# ATMEGA2560.net
KiCad netlist of a schematic drawn in Altium Designer
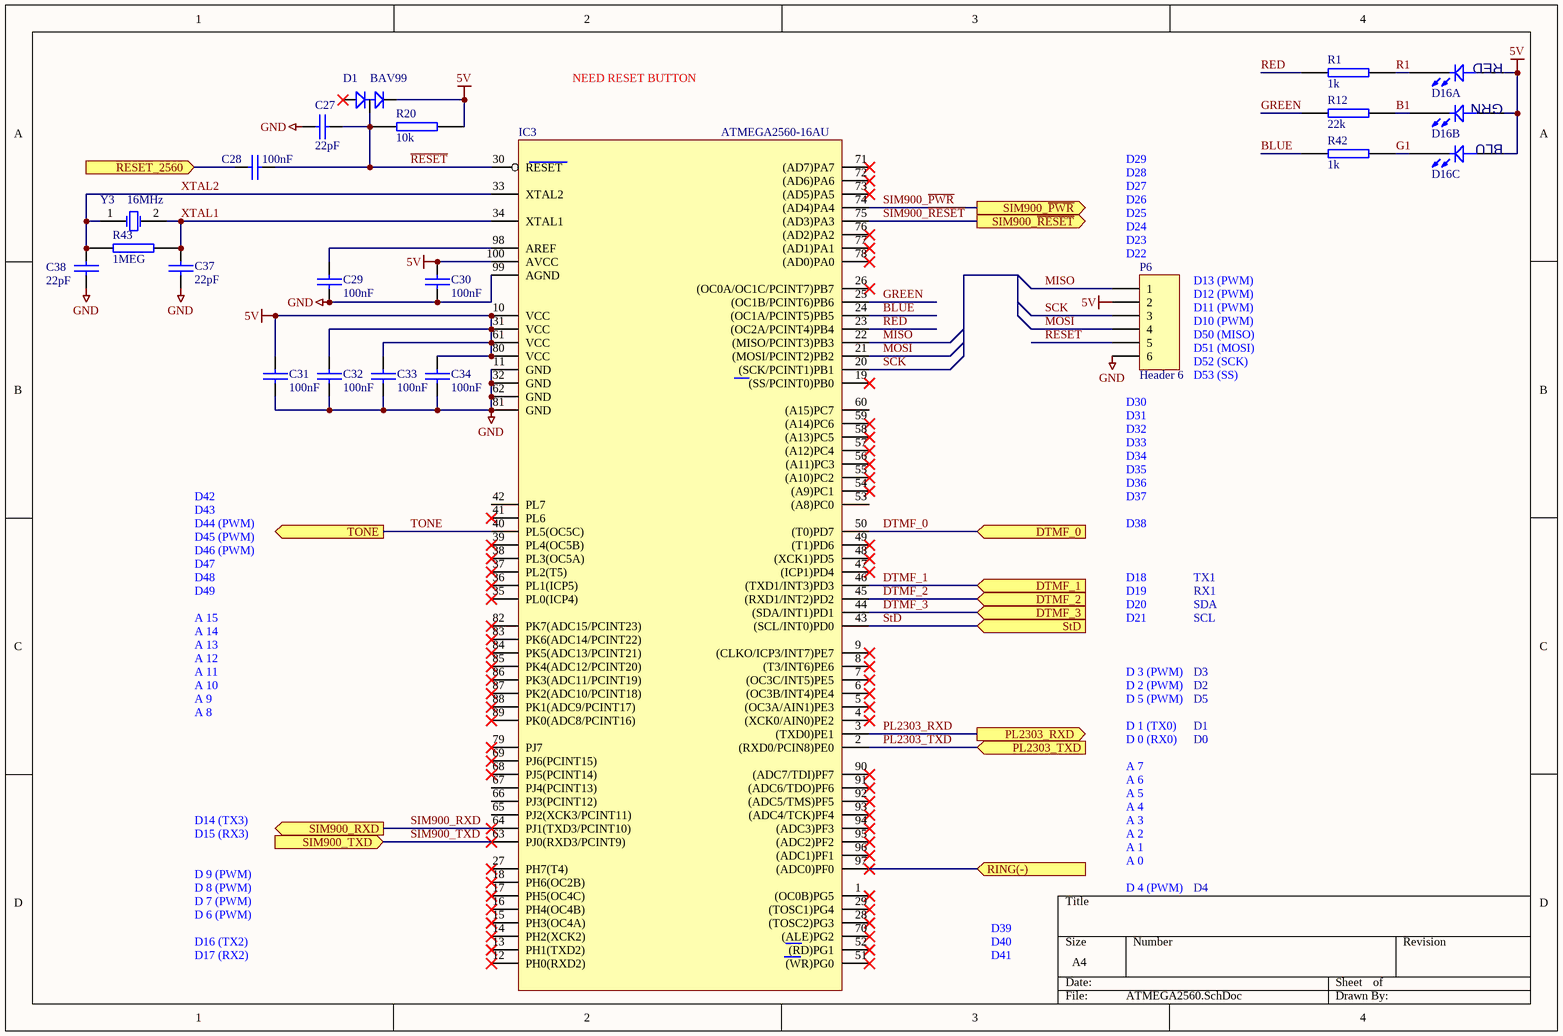
[diagram p0: ATMEGA2560.SchDoc]

(export (version "E")
  (design (tool "Eeschema 10.0.6"))
  (components
    (comp (ref "C27")
      (value "22pF")
      (footprint "CAP (3D) - 0603")
      (description "CAPACITOR SMD 0603")
      (fields (field (name "MOUSER PART NO.") "81-GCM188R71C104KA7D") (field (name "MANUFACTURER") "Murata"))
      (libsource (lib "NASCO Capacitors") (part "CAP SMD 0603 100nF"))
    )
    (comp (ref "C28")
      (value "100nF")
      (footprint "CAP (3D) - 0603")
      (description "CAPACITOR SMD 0603")
      (fields (field (name "MOUSER PART NO.") "81-GCM188R71C104KA7D") (field (name "MANUFACTURER") "Murata"))
      (libsource (lib "NASCO Capacitors") (part "CAP SMD 0603 100nF"))
    )
    (comp (ref "C29")
      (value "100nF")
      (footprint "CAP (3D) - 0603")
      (description "CAPACITOR SMD 0603")
      (fields (field (name "MOUSER PART NO.") "81-GCM188R71C104KA7D") (field (name "MANUFACTURER") "Murata"))
      (libsource (lib "NASCO Capacitors") (part "CAP SMD 0603 100nF"))
    )
    (comp (ref "C30")
      (value "100nF")
      (footprint "CAP (3D) - 0603")
      (description "CAPACITOR SMD 0603")
      (fields (field (name "MOUSER PART NO.") "81-GCM188R71C104KA7D") (field (name "MANUFACTURER") "Murata"))
      (libsource (lib "NASCO Capacitors") (part "CAP SMD 0603 100nF"))
    )
    (comp (ref "C31")
      (value "100nF")
      (footprint "CAP (3D) - 0603")
      (description "CAPACITOR SMD 0603")
      (fields (field (name "MOUSER PART NO.") "81-GCM188R71C104KA7D") (field (name "MANUFACTURER") "Murata"))
      (libsource (lib "NASCO Capacitors") (part "CAP SMD 0603 100nF"))
    )
    (comp (ref "C32")
      (value "100nF")
      (footprint "CAP (3D) - 0603")
      (description "CAPACITOR SMD 0603")
      (fields (field (name "MOUSER PART NO.") "81-GCM188R71C104KA7D") (field (name "MANUFACTURER") "Murata"))
      (libsource (lib "NASCO Capacitors") (part "CAP SMD 0603 100nF"))
    )
    (comp (ref "C33")
      (value "100nF")
      (footprint "CAP (3D) - 0603")
      (description "CAPACITOR SMD 0603")
      (fields (field (name "MOUSER PART NO.") "81-GCM188R71C104KA7D") (field (name "MANUFACTURER") "Murata"))
      (libsource (lib "NASCO Capacitors") (part "CAP SMD 0603 100nF"))
    )
    (comp (ref "C34")
      (value "100nF")
      (footprint "CAP (3D) - 0603")
      (description "CAPACITOR SMD 0603")
      (fields (field (name "MOUSER PART NO.") "81-GCM188R71C104KA7D") (field (name "MANUFACTURER") "Murata"))
      (libsource (lib "NASCO Capacitors") (part "CAP SMD 0603 100nF"))
    )
    (comp (ref "C37")
      (value "22pF")
      (footprint "CAP (3D) - 0603")
      (description "CAPACITOR SMD 0603")
      (fields
        (field (name "MANUFACTURER") "Vishay")
        (field (name "MANUFACTURER PART NO.") "VJ0603A220JXACW1BC")
      )
      (libsource (lib "NASCO Capacitors") (part "CAP SMD 0603 1nF"))
    )
    (comp (ref "C38")
      (value "22pF")
      (footprint "CAP (3D) - 0603")
      (description "CAPACITOR SMD 0603")
      (fields
        (field (name "MANUFACTURER") "Vishay")
        (field (name "MANUFACTURER PART NO.") "VJ0603A220JXACW1BC")
      )
      (libsource (lib "NASCO Capacitors") (part "CAP SMD 0603 1nF"))
    )
    (comp (ref "D1")
      (value "BAV99")
      (footprint "SOT23-3L")
      (description "DUAL DIODE, BAV99")
      (fields
        (field (name "MOUSER PART NO.") "771-BAV99/T3")
        (field (name "MANUFACTURER") "FAIRCHILD SEMICONDUCTOR")
      )
      (libsource (lib "NASCO") (part "BAV99"))
    )
    (comp (ref "D16")
      (value "RGB 5mm")
      (footprint "LED(3D) 5MM RIGHT ANGLE (RGB) - COMMON ANODE")
      (fields (field (name "MANUFACTURER") "ANY - COMMON ANODE"))
      (libsource (lib "NASCO") (part "RGB_5mm"))
    )
    (comp (ref "IC3")
      (value "ATMEGA2560-16AU")
      (footprint "TQFP100")
      (fields
        (field (name "MANUFACTURER") "Atmel")
        (field (name "MANUFACTURER PART NO.") "ATmega2560-16AU")
        (field (name "MOUSER PART NO.") "556-ATMEGA2560-16AU")
      )
      (libsource (lib "NASCO") (part "ATMEGA25602560-16AU"))
    )
    (comp (ref "P6")
      (value "Header 6")
      (footprint "HDR2X3 (3D)")
      (description "Header, 6-Pin")
      (libsource (lib "Miscellaneous Connectors") (part "Header 6"))
    )
    (comp (ref "R1")
      (value "1k")
      (footprint "RES (3D) - 0603")
      (description "RESISTOR SMD 0603")
      (fields (field (name "MOUSER PART NO.") "652-CR0603-JW-102ELF") (field (name "MANUFACTURER") "Bourns"))
      (libsource (lib "NASCO Resistors") (part "RES SMD 0603 10k"))
    )
    (comp (ref "R12")
      (value "22k")
      (footprint "RES (3D) - 0603")
      (description "RESISTOR SMD 0603")
      (fields (field (name "MOUSER PART NO.") "652-CR0603FX-4223ELF") (field (name "MANUFACTURER") "Bourns"))
      (libsource (lib "NASCO Resistors") (part "RES SMD 0603 10k"))
    )
    (comp (ref "R20")
      (value "10k")
      (footprint "RES (3D) - 0603")
      (description "RESISTOR SMD 0603 10k")
      (fields (field (name "MOUSER PART NO.") "652-CR0603FX-1002ELF") (field (name "MANUFACTURER") "Bourns"))
      (libsource (lib "NASCO Resistors") (part "RES SMD 0603 10k"))
    )
    (comp (ref "R42")
      (value "1k")
      (footprint "RES (3D) - 0603")
      (description "RESISTOR SMD 0603")
      (fields (field (name "MOUSER PART NO.") "652-CR0603-JW-102ELF") (field (name "MANUFACTURER") "Bourns"))
      (libsource (lib "NASCO Resistors") (part "RES SMD 0603 10k"))
    )
    (comp (ref "R43")
      (value "1MEG")
      (footprint "RES (3D) - 0603")
      (description "RESISTOR SMD 0603 0R")
      (fields
        (field (name "MANUFACTURER") "Bourns")
        (field (name "MANUFACTURER PART NO.") "CR0603-FX-1004ELF")
      )
      (libsource (lib "NASCO Resistors") (part "RES SMD 0603 0R"))
    )
    (comp (ref "Y3")
      (value "16MHz")
      (footprint "HC49/4H_SMX")
      (description "Crystal Oscillator")
      (fields (field (name "MOUSER PART NO.") "520-CSM1600-20-X") (field (name "MANUFACTURER") "ECS"))
      (libsource (lib "Miscellaneous Devices") (part "XTAL"))
    )
  )
  (nets
    (net (code "1") (name "/B1") (class "Default")
      (node (ref "D16") (pin "4") (pinfunction "K_4") (pintype "passive"))
      (node (ref "R12") (pin "2") (pinfunction "2_2") (pintype "passive"))
    )
    (net (code "2") (name "/BLUE") (class "Default")
      (node (ref "IC3") (pin "24") (pinfunction "(OC1A/PCINT5)PB5_24") (pintype "passive"))
      (node (ref "R42") (pin "1") (pinfunction "1_1") (pintype "passive"))
    )
    (net (code "3") (name "/DTMF_0") (class "Default")
      (node (ref "IC3") (pin "50") (pinfunction "(T0)PD7_50") (pintype "passive"))
    )
    (net (code "4") (name "/DTMF_1") (class "Default")
      (node (ref "IC3") (pin "46") (pinfunction "(TXD1/INT3)PD3_46") (pintype "passive"))
    )
    (net (code "5") (name "/DTMF_2") (class "Default")
      (node (ref "IC3") (pin "45") (pinfunction "(RXD1/INT2)PD2_45") (pintype "passive"))
    )
    (net (code "6") (name "/DTMF_3") (class "Default")
      (node (ref "IC3") (pin "44") (pinfunction "(SDA/INT1)PD1_44") (pintype "passive"))
    )
    (net (code "7") (name "/G1") (class "Default")
      (node (ref "D16") (pin "3") (pinfunction "K_3") (pintype "passive"))
      (node (ref "R42") (pin "2") (pinfunction "2_2") (pintype "passive"))
    )
    (net (code "8") (name "/GREEN") (class "Default")
      (node (ref "IC3") (pin "25") (pinfunction "(OC1B/PCINT6)PB6_25") (pintype "passive"))
      (node (ref "R12") (pin "1") (pinfunction "1_1") (pintype "passive"))
    )
    (net (code "9") (name "/MISO") (class "Default")
      (node (ref "IC3") (pin "22") (pinfunction "(MISO/PCINT3)PB3_22") (pintype "passive"))
      (node (ref "P6") (pin "1") (pinfunction "1_1") (pintype "passive"))
    )
    (net (code "10") (name "/MOSI") (class "Default")
      (node (ref "IC3") (pin "21") (pinfunction "(MOSI/PCINT2)PB2_21") (pintype "passive"))
      (node (ref "P6") (pin "4") (pinfunction "4_4") (pintype "passive"))
    )
    (net (code "11") (name "/PL2303_RXD") (class "Default")
      (node (ref "IC3") (pin "3") (pinfunction "(TXD0)PE1_3") (pintype "passive"))
    )
    (net (code "12") (name "/PL2303_TXD") (class "Default")
      (node (ref "IC3") (pin "2") (pinfunction "(RXD0/PCIN8)PE0_2") (pintype "passive"))
    )
    (net (code "13") (name "/R1") (class "Default")
      (node (ref "D16") (pin "1") (pinfunction "K_1") (pintype "passive"))
      (node (ref "R1") (pin "2") (pinfunction "2_2") (pintype "passive"))
    )
    (net (code "14") (name "/RED") (class "Default")
      (node (ref "IC3") (pin "23") (pinfunction "(OC2A/PCINT4)PB4_23") (pintype "passive"))
      (node (ref "R1") (pin "1") (pinfunction "1_1") (pintype "passive"))
    )
    (net (code "15") (name "/RESET_2560") (class "Default")
      (node (ref "C28") (pin "1") (pinfunction "1_1") (pintype "passive"))
    )
    (net (code "16") (name "/RING(-)") (class "Default")
      (node (ref "IC3") (pin "97") (pinfunction "(ADC0)PF0_97") (pintype "passive+no_connect"))
    )
    (net (code "17") (name "/SCK") (class "Default")
      (node (ref "IC3") (pin "20") (pinfunction "(SCK/PCINT1)PB1_20") (pintype "passive"))
      (node (ref "P6") (pin "3") (pinfunction "3_3") (pintype "passive"))
    )
    (net (code "18") (name "/SIM900_RXD") (class "Default")
      (node (ref "IC3") (pin "64") (pinfunction "PJ1(TXD3/PCINT10)_64") (pintype "passive+no_connect"))
    )
    (net (code "19") (name "/SIM900_TXD") (class "Default")
      (node (ref "IC3") (pin "63") (pinfunction "PJ0(RXD3/PCINT9)_63") (pintype "passive+no_connect"))
    )
    (net (code "20") (name "/SIM900_~{PWR}") (class "Default")
      (node (ref "IC3") (pin "74") (pinfunction "(AD4)PA4_74") (pintype "passive"))
    )
    (net (code "21") (name "/SIM900_~{RESET}") (class "Default")
      (node (ref "IC3") (pin "75") (pinfunction "(AD3)PA3_75") (pintype "passive"))
    )
    (net (code "22") (name "/StD") (class "Default")
      (node (ref "IC3") (pin "43") (pinfunction "(SCL/INT0)PD0_43") (pintype "passive"))
    )
    (net (code "23") (name "/TONE") (class "Default")
      (node (ref "IC3") (pin "40") (pinfunction "PL5(OC5C)_40") (pintype "passive"))
    )
    (net (code "24") (name "/XTAL1") (class "Default")
      (node (ref "C37") (pin "1") (pinfunction "1_1") (pintype "passive"))
      (node (ref "IC3") (pin "34") (pinfunction "XTAL1_34") (pintype "passive"))
      (node (ref "R43") (pin "2") (pinfunction "2_2") (pintype "passive"))
      (node (ref "Y3") (pin "2") (pinfunction "OSC2_2") (pintype "passive"))
    )
    (net (code "25") (name "/XTAL2") (class "Default")
      (node (ref "C38") (pin "1") (pinfunction "1_1") (pintype "passive"))
      (node (ref "IC3") (pin "33") (pinfunction "XTAL2_33") (pintype "passive"))
      (node (ref "R43") (pin "1") (pinfunction "1_1") (pintype "passive"))
      (node (ref "Y3") (pin "1") (pinfunction "OSC1_1") (pintype "passive"))
    )
    (net (code "26") (name "/~{RESET}") (class "Default")
      (node (ref "C27") (pin "2") (pinfunction "2_2") (pintype "passive"))
      (node (ref "C28") (pin "2") (pinfunction "2_2") (pintype "passive"))
      (node (ref "D1") (pin "3") (pinfunction "C1/A2_3") (pintype "passive"))
      (node (ref "IC3") (pin "30") (pinfunction "RESET_30") (pintype "passive"))
      (node (ref "P6") (pin "5") (pinfunction "5_5") (pintype "passive"))
      (node (ref "R20") (pin "1") (pinfunction "1_1") (pintype "passive"))
    )
    (net (code "27") (name "5V") (class "Default")
      (node (ref "C30") (pin "1") (pinfunction "1_1") (pintype "passive"))
      (node (ref "C31") (pin "1") (pinfunction "1_1") (pintype "passive"))
      (node (ref "C32") (pin "1") (pinfunction "1_1") (pintype "passive"))
      (node (ref "C33") (pin "1") (pinfunction "1_1") (pintype "passive"))
      (node (ref "C34") (pin "1") (pinfunction "1_1") (pintype "passive"))
      (node (ref "D1") (pin "2") (pinfunction "C2_2") (pintype "passive"))
      (node (ref "D16") (pin "2") (pinfunction "A_2") (pintype "passive"))
      (node (ref "IC3") (pin "10") (pinfunction "VCC_10") (pintype "passive"))
      (node (ref "IC3") (pin "100") (pinfunction "AVCC_100") (pintype "passive"))
      (node (ref "IC3") (pin "31") (pinfunction "VCC_31") (pintype "passive"))
      (node (ref "IC3") (pin "61") (pinfunction "VCC_61") (pintype "passive"))
      (node (ref "IC3") (pin "80") (pinfunction "VCC_80") (pintype "passive"))
      (node (ref "P6") (pin "2") (pinfunction "2_2") (pintype "passive"))
      (node (ref "R20") (pin "2") (pinfunction "2_2") (pintype "passive"))
    )
    (net (code "28") (name "GND") (class "Default")
      (node (ref "C27") (pin "1") (pinfunction "1_1") (pintype "passive"))
      (node (ref "C29") (pin "2") (pinfunction "2_2") (pintype "passive"))
      (node (ref "C30") (pin "2") (pinfunction "2_2") (pintype "passive"))
      (node (ref "C31") (pin "2") (pinfunction "2_2") (pintype "passive"))
      (node (ref "C32") (pin "2") (pinfunction "2_2") (pintype "passive"))
      (node (ref "C33") (pin "2") (pinfunction "2_2") (pintype "passive"))
      (node (ref "C34") (pin "2") (pinfunction "2_2") (pintype "passive"))
      (node (ref "C37") (pin "2") (pinfunction "2_2") (pintype "passive"))
      (node (ref "C38") (pin "2") (pinfunction "2_2") (pintype "passive"))
      (node (ref "IC3") (pin "11") (pinfunction "GND_11") (pintype "passive"))
      (node (ref "IC3") (pin "32") (pinfunction "GND_32") (pintype "passive"))
      (node (ref "IC3") (pin "62") (pinfunction "GND_62") (pintype "passive"))
      (node (ref "IC3") (pin "81") (pinfunction "GND_81") (pintype "passive"))
      (node (ref "IC3") (pin "99") (pinfunction "AGND_99") (pintype "passive"))
      (node (ref "P6") (pin "6") (pinfunction "6_6") (pintype "passive"))
    )
    (net (code "29") (name "Net-(IC3-AREF)") (class "Default")
      (node (ref "C29") (pin "1") (pinfunction "1_1") (pintype "passive"))
      (node (ref "IC3") (pin "98") (pinfunction "AREF_98") (pintype "passive"))
    )
    (net (code "30") (name "unconnected-(D1-A1-Pad1)") (class "Default")
      (node (ref "D1") (pin "1") (pinfunction "A1_1") (pintype "passive+no_connect"))
    )
    (net (code "31") (name "unconnected-(IC3-(A8)PC0-Pad53)") (class "Default")
      (node (ref "IC3") (pin "53") (pinfunction "(A8)PC0_53") (pintype "passive"))
    )
    (net (code "32") (name "unconnected-(IC3-(A9)PC1-Pad54)") (class "Default")
      (node (ref "IC3") (pin "54") (pinfunction "(A9)PC1_54") (pintype "passive+no_connect"))
    )
    (net (code "33") (name "unconnected-(IC3-(A10)PC2-Pad55)") (class "Default")
      (node (ref "IC3") (pin "55") (pinfunction "(A10)PC2_55") (pintype "passive+no_connect"))
    )
    (net (code "34") (name "unconnected-(IC3-(A11)PC3-Pad56)") (class "Default")
      (node (ref "IC3") (pin "56") (pinfunction "(A11)PC3_56") (pintype "passive+no_connect"))
    )
    (net (code "35") (name "unconnected-(IC3-(A12)PC4-Pad57)") (class "Default")
      (node (ref "IC3") (pin "57") (pinfunction "(A12)PC4_57") (pintype "passive+no_connect"))
    )
    (net (code "36") (name "unconnected-(IC3-(A13)PC5-Pad58)") (class "Default")
      (node (ref "IC3") (pin "58") (pinfunction "(A13)PC5_58") (pintype "passive+no_connect"))
    )
    (net (code "37") (name "unconnected-(IC3-(A14)PC6-Pad59)") (class "Default")
      (node (ref "IC3") (pin "59") (pinfunction "(A14)PC6_59") (pintype "passive+no_connect"))
    )
    (net (code "38") (name "unconnected-(IC3-(A15)PC7-Pad60)") (class "Default")
      (node (ref "IC3") (pin "60") (pinfunction "(A15)PC7_60") (pintype "passive"))
    )
    (net (code "39") (name "unconnected-(IC3-(AD0)PA0-Pad78)") (class "Default")
      (node (ref "IC3") (pin "78") (pinfunction "(AD0)PA0_78") (pintype "passive+no_connect"))
    )
    (net (code "40") (name "unconnected-(IC3-(AD1)PA1-Pad77)") (class "Default")
      (node (ref "IC3") (pin "77") (pinfunction "(AD1)PA1_77") (pintype "passive+no_connect"))
    )
    (net (code "41") (name "unconnected-(IC3-(AD2)PA2-Pad76)") (class "Default")
      (node (ref "IC3") (pin "76") (pinfunction "(AD2)PA2_76") (pintype "passive+no_connect"))
    )
    (net (code "42") (name "unconnected-(IC3-(AD5)PA5-Pad73)") (class "Default")
      (node (ref "IC3") (pin "73") (pinfunction "(AD5)PA5_73") (pintype "passive+no_connect"))
    )
    (net (code "43") (name "unconnected-(IC3-(AD6)PA6-Pad72)") (class "Default")
      (node (ref "IC3") (pin "72") (pinfunction "(AD6)PA6_72") (pintype "passive+no_connect"))
    )
    (net (code "44") (name "unconnected-(IC3-(AD7)PA7-Pad71)") (class "Default")
      (node (ref "IC3") (pin "71") (pinfunction "(AD7)PA7_71") (pintype "passive+no_connect"))
    )
    (net (code "45") (name "unconnected-(IC3-(ADC1)PF1-Pad96)") (class "Default")
      (node (ref "IC3") (pin "96") (pinfunction "(ADC1)PF1_96") (pintype "passive+no_connect"))
    )
    (net (code "46") (name "unconnected-(IC3-(ADC2)PF2-Pad95)") (class "Default")
      (node (ref "IC3") (pin "95") (pinfunction "(ADC2)PF2_95") (pintype "passive+no_connect"))
    )
    (net (code "47") (name "unconnected-(IC3-(ADC3)PF3-Pad94)") (class "Default")
      (node (ref "IC3") (pin "94") (pinfunction "(ADC3)PF3_94") (pintype "passive+no_connect"))
    )
    (net (code "48") (name "unconnected-(IC3-(ADC4{slash}TCK)PF4-Pad93)") (class "Default")
      (node (ref "IC3") (pin "93") (pinfunction "(ADC4/TCK)PF4_93") (pintype "passive+no_connect"))
    )
    (net (code "49") (name "unconnected-(IC3-(ADC5{slash}TMS)PF5-Pad92)") (class "Default")
      (node (ref "IC3") (pin "92") (pinfunction "(ADC5/TMS)PF5_92") (pintype "passive+no_connect"))
    )
    (net (code "50") (name "unconnected-(IC3-(ADC6{slash}TDO)PF6-Pad91)") (class "Default")
      (node (ref "IC3") (pin "91") (pinfunction "(ADC6/TDO)PF6_91") (pintype "passive+no_connect"))
    )
    (net (code "51") (name "unconnected-(IC3-(ADC7{slash}TDI)PF7-Pad90)") (class "Default")
      (node (ref "IC3") (pin "90") (pinfunction "(ADC7/TDI)PF7_90") (pintype "passive+no_connect"))
    )
    (net (code "52") (name "unconnected-(IC3-(ALE)PG2-Pad70)") (class "Default")
      (node (ref "IC3") (pin "70") (pinfunction "(ALE)PG2_70") (pintype "passive+no_connect"))
    )
    (net (code "53") (name "unconnected-(IC3-(CLKO{slash}ICP3{slash}INT7)PE7-Pad9)") (class "Default")
      (node (ref "IC3") (pin "9") (pinfunction "(CLKO/ICP3/INT7)PE7_9") (pintype "passive+no_connect"))
    )
    (net (code "54") (name "unconnected-(IC3-(ICP1)PD4-Pad47)") (class "Default")
      (node (ref "IC3") (pin "47") (pinfunction "(ICP1)PD4_47") (pintype "passive+no_connect"))
    )
    (net (code "55") (name "unconnected-(IC3-(OC0A{slash}OC1C{slash}PCINT7)PB7-Pad26)") (class "Default")
      (node (ref "IC3") (pin "26") (pinfunction "(OC0A/OC1C/PCINT7)PB7_26") (pintype "passive+no_connect"))
    )
    (net (code "56") (name "unconnected-(IC3-(OC0B)PG5-Pad1)") (class "Default")
      (node (ref "IC3") (pin "1") (pinfunction "(OC0B)PG5_1") (pintype "passive+no_connect"))
    )
    (net (code "57") (name "unconnected-(IC3-(OC3A{slash}AIN1)PE3-Pad5)") (class "Default")
      (node (ref "IC3") (pin "5") (pinfunction "(OC3A/AIN1)PE3_5") (pintype "passive+no_connect"))
    )
    (net (code "58") (name "unconnected-(IC3-(OC3B{slash}INT4)PE4-Pad6)") (class "Default")
      (node (ref "IC3") (pin "6") (pinfunction "(OC3B/INT4)PE4_6") (pintype "passive+no_connect"))
    )
    (net (code "59") (name "unconnected-(IC3-(OC3C{slash}INT5)PE5-Pad7)") (class "Default")
      (node (ref "IC3") (pin "7") (pinfunction "(OC3C/INT5)PE5_7") (pintype "passive+no_connect"))
    )
    (net (code "60") (name "unconnected-(IC3-(RD)PG1-Pad52)") (class "Default")
      (node (ref "IC3") (pin "52") (pinfunction "(RD)PG1_52") (pintype "passive+no_connect"))
    )
    (net (code "61") (name "unconnected-(IC3-(SS{slash}PCINT0)PB0-Pad19)") (class "Default")
      (node (ref "IC3") (pin "19") (pinfunction "(SS/PCINT0)PB0_19") (pintype "passive+no_connect"))
    )
    (net (code "62") (name "unconnected-(IC3-(T1)PD6-Pad49)") (class "Default")
      (node (ref "IC3") (pin "49") (pinfunction "(T1)PD6_49") (pintype "passive+no_connect"))
    )
    (net (code "63") (name "unconnected-(IC3-(T3{slash}INT6)PE6-Pad8)") (class "Default")
      (node (ref "IC3") (pin "8") (pinfunction "(T3/INT6)PE6_8") (pintype "passive+no_connect"))
    )
    (net (code "64") (name "unconnected-(IC3-(TOSC1)PG4-Pad29)") (class "Default")
      (node (ref "IC3") (pin "29") (pinfunction "(TOSC1)PG4_29") (pintype "passive+no_connect"))
    )
    (net (code "65") (name "unconnected-(IC3-(TOSC2)PG3-Pad28)") (class "Default")
      (node (ref "IC3") (pin "28") (pinfunction "(TOSC2)PG3_28") (pintype "passive+no_connect"))
    )
    (net (code "66") (name "unconnected-(IC3-(WR)PG0-Pad51)") (class "Default")
      (node (ref "IC3") (pin "51") (pinfunction "(WR)PG0_51") (pintype "passive+no_connect"))
    )
    (net (code "67") (name "unconnected-(IC3-(XCK0{slash}AIN0)PE2-Pad4)") (class "Default")
      (node (ref "IC3") (pin "4") (pinfunction "(XCK0/AIN0)PE2_4") (pintype "passive+no_connect"))
    )
    (net (code "68") (name "unconnected-(IC3-(XCK1)PD5-Pad48)") (class "Default")
      (node (ref "IC3") (pin "48") (pinfunction "(XCK1)PD5_48") (pintype "passive+no_connect"))
    )
    (net (code "69") (name "unconnected-(IC3-PH0(RXD2)-Pad12)") (class "Default")
      (node (ref "IC3") (pin "12") (pinfunction "PH0(RXD2)_12") (pintype "passive+no_connect"))
    )
    (net (code "70") (name "unconnected-(IC3-PH1(TXD2)-Pad13)") (class "Default")
      (node (ref "IC3") (pin "13") (pinfunction "PH1(TXD2)_13") (pintype "passive+no_connect"))
    )
    (net (code "71") (name "unconnected-(IC3-PH2(XCK2)-Pad14)") (class "Default")
      (node (ref "IC3") (pin "14") (pinfunction "PH2(XCK2)_14") (pintype "passive+no_connect"))
    )
    (net (code "72") (name "unconnected-(IC3-PH3(OC4A)-Pad15)") (class "Default")
      (node (ref "IC3") (pin "15") (pinfunction "PH3(OC4A)_15") (pintype "passive+no_connect"))
    )
    (net (code "73") (name "unconnected-(IC3-PH4(OC4B)-Pad16)") (class "Default")
      (node (ref "IC3") (pin "16") (pinfunction "PH4(OC4B)_16") (pintype "passive+no_connect"))
    )
    (net (code "74") (name "unconnected-(IC3-PH5(OC4C)-Pad17)") (class "Default")
      (node (ref "IC3") (pin "17") (pinfunction "PH5(OC4C)_17") (pintype "passive+no_connect"))
    )
    (net (code "75") (name "unconnected-(IC3-PH6(OC2B)-Pad18)") (class "Default")
      (node (ref "IC3") (pin "18") (pinfunction "PH6(OC2B)_18") (pintype "passive+no_connect"))
    )
    (net (code "76") (name "unconnected-(IC3-PH7(T4)-Pad27)") (class "Default")
      (node (ref "IC3") (pin "27") (pinfunction "PH7(T4)_27") (pintype "passive+no_connect"))
    )
    (net (code "77") (name "unconnected-(IC3-PJ2(XCK3{slash}PCINT11)-Pad65)") (class "Default")
      (node (ref "IC3") (pin "65") (pinfunction "PJ2(XCK3/PCINT11)_65") (pintype "passive"))
    )
    (net (code "78") (name "unconnected-(IC3-PJ3(PCINT12)-Pad66)") (class "Default")
      (node (ref "IC3") (pin "66") (pinfunction "PJ3(PCINT12)_66") (pintype "passive"))
    )
    (net (code "79") (name "unconnected-(IC3-PJ4(PCINT13)-Pad67)") (class "Default")
      (node (ref "IC3") (pin "67") (pinfunction "PJ4(PCINT13)_67") (pintype "passive"))
    )
    (net (code "80") (name "unconnected-(IC3-PJ5(PCINT14)-Pad68)") (class "Default")
      (node (ref "IC3") (pin "68") (pinfunction "PJ5(PCINT14)_68") (pintype "passive+no_connect"))
    )
    (net (code "81") (name "unconnected-(IC3-PJ6(PCINT15)-Pad69)") (class "Default")
      (node (ref "IC3") (pin "69") (pinfunction "PJ6(PCINT15)_69") (pintype "passive+no_connect"))
    )
    (net (code "82") (name "unconnected-(IC3-PJ7-Pad79)") (class "Default")
      (node (ref "IC3") (pin "79") (pinfunction "PJ7_79") (pintype "passive+no_connect"))
    )
    (net (code "83") (name "unconnected-(IC3-PK0(ADC8{slash}PCINT16)-Pad89)") (class "Default")
      (node (ref "IC3") (pin "89") (pinfunction "PK0(ADC8/PCINT16)_89") (pintype "passive+no_connect"))
    )
    (net (code "84") (name "unconnected-(IC3-PK1(ADC9{slash}PCINT17)-Pad88)") (class "Default")
      (node (ref "IC3") (pin "88") (pinfunction "PK1(ADC9/PCINT17)_88") (pintype "passive+no_connect"))
    )
    (net (code "85") (name "unconnected-(IC3-PK2(ADC10{slash}PCINT18)-Pad87)") (class "Default")
      (node (ref "IC3") (pin "87") (pinfunction "PK2(ADC10/PCINT18)_87") (pintype "passive+no_connect"))
    )
    (net (code "86") (name "unconnected-(IC3-PK3(ADC11{slash}PCINT19)-Pad86)") (class "Default")
      (node (ref "IC3") (pin "86") (pinfunction "PK3(ADC11/PCINT19)_86") (pintype "passive+no_connect"))
    )
    (net (code "87") (name "unconnected-(IC3-PK4(ADC12{slash}PCINT20)-Pad85)") (class "Default")
      (node (ref "IC3") (pin "85") (pinfunction "PK4(ADC12/PCINT20)_85") (pintype "passive+no_connect"))
    )
    (net (code "88") (name "unconnected-(IC3-PK5(ADC13{slash}PCINT21)-Pad84)") (class "Default")
      (node (ref "IC3") (pin "84") (pinfunction "PK5(ADC13/PCINT21)_84") (pintype "passive+no_connect"))
    )
    (net (code "89") (name "unconnected-(IC3-PK6(ADC14{slash}PCINT22)-Pad83)") (class "Default")
      (node (ref "IC3") (pin "83") (pinfunction "PK6(ADC14/PCINT22)_83") (pintype "passive+no_connect"))
    )
    (net (code "90") (name "unconnected-(IC3-PK7(ADC15{slash}PCINT23)-Pad82)") (class "Default")
      (node (ref "IC3") (pin "82") (pinfunction "PK7(ADC15/PCINT23)_82") (pintype "passive+no_connect"))
    )
    (net (code "91") (name "unconnected-(IC3-PL0(ICP4)-Pad35)") (class "Default")
      (node (ref "IC3") (pin "35") (pinfunction "PL0(ICP4)_35") (pintype "passive+no_connect"))
    )
    (net (code "92") (name "unconnected-(IC3-PL1(ICP5)-Pad36)") (class "Default")
      (node (ref "IC3") (pin "36") (pinfunction "PL1(ICP5)_36") (pintype "passive+no_connect"))
    )
    (net (code "93") (name "unconnected-(IC3-PL2(T5)-Pad37)") (class "Default")
      (node (ref "IC3") (pin "37") (pinfunction "PL2(T5)_37") (pintype "passive+no_connect"))
    )
    (net (code "94") (name "unconnected-(IC3-PL3(OC5A)-Pad38)") (class "Default")
      (node (ref "IC3") (pin "38") (pinfunction "PL3(OC5A)_38") (pintype "passive+no_connect"))
    )
    (net (code "95") (name "unconnected-(IC3-PL4(OC5B)-Pad39)") (class "Default")
      (node (ref "IC3") (pin "39") (pinfunction "PL4(OC5B)_39") (pintype "passive+no_connect"))
    )
    (net (code "96") (name "unconnected-(IC3-PL6-Pad41)") (class "Default")
      (node (ref "IC3") (pin "41") (pinfunction "PL6_41") (pintype "passive+no_connect"))
    )
    (net (code "97") (name "unconnected-(IC3-PL7-Pad42)") (class "Default")
      (node (ref "IC3") (pin "42") (pinfunction "PL7_42") (pintype "passive"))
    )
  )
)
